# DUAL_M2_LEDS.net
KiCad netlist of a schematic drawn in EAGLE
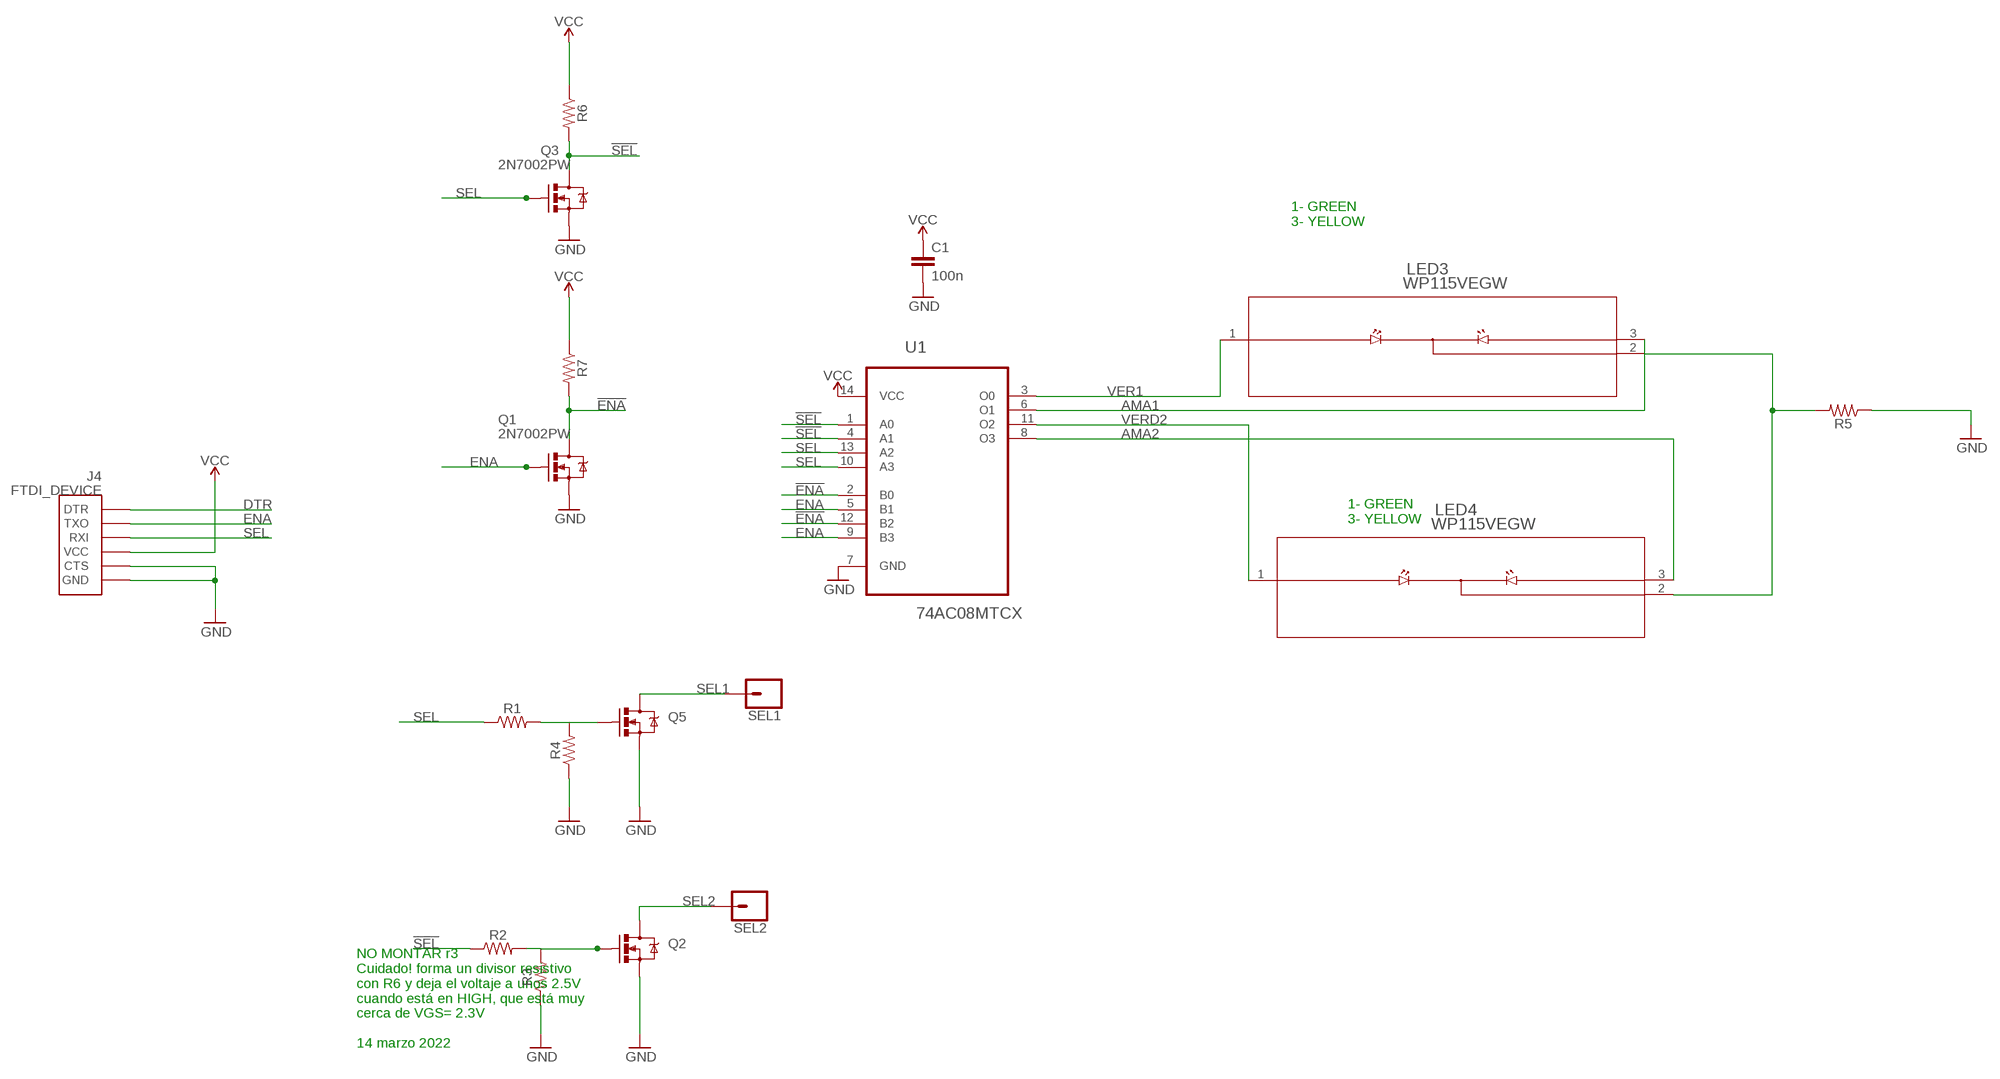
[diagram p0: schematic, sheet 1, part 1 of 2]
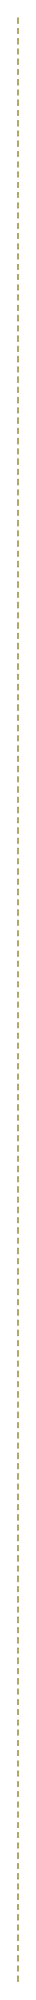
[diagram p1: schematic, sheet 1, part 2 of 2]

(export (version "E")
  (design (tool "Eeschema 10.0.6"))
  (components
    (comp (ref "C1")
      (value "100n")
      (footprint "eagle-import:0805")
      (libsource (lib "eagle-import") (part "CAPACITOR-N0805"))
    )
    (comp (ref "J4")
      (value "FTDI_DEVICE")
      (footprint "eagle-import:FTDI_DEVICE_SIDE")
      (libsource (lib "eagle-import") (part "FTDI_DEVICE"))
    )
    (comp (ref "LED3")
      (value "WP115VEGW")
      (footprint "eagle-import:WP115VEGW_KNB")
      (fields (field (name "COPYRIGHT") "Copyright (C) 2018 Accelerated Designs. All rights reserved"))
      (libsource (lib "eagle-import") (part "WP115VEGW"))
    )
    (comp (ref "LED4")
      (value "WP115VEGW")
      (footprint "eagle-import:WP115VEGW_KNB")
      (fields (field (name "COPYRIGHT") "Copyright (C) 2018 Accelerated Designs. All rights reserved"))
      (libsource (lib "eagle-import") (part "WP115VEGW"))
    )
    (comp (ref "Q1")
      (value "2N7002PW")
      (footprint "eagle-import:SOT323")
      (libsource (lib "eagle-import") (part "MOSFET-NCHANNEL2N7002PW"))
    )
    (comp (ref "Q2")
      (value "2N7002PW")
      (footprint "eagle-import:SOT323")
      (libsource (lib "eagle-import") (part "MOSFET-NCHANNEL2N7002PW"))
    )
    (comp (ref "Q3")
      (value "2N7002PW")
      (footprint "eagle-import:SOT323")
      (libsource (lib "eagle-import") (part "MOSFET-NCHANNEL2N7002PW"))
    )
    (comp (ref "Q5")
      (value "2N7002PW")
      (footprint "eagle-import:SOT323")
      (libsource (lib "eagle-import") (part "MOSFET-NCHANNEL2N7002PW"))
    )
    (comp (ref "R1")
      (value "RESISTOR0805")
      (footprint "eagle-import:0805")
      (libsource (lib "eagle-import") (part "RESISTOR0805"))
    )
    (comp (ref "R2")
      (value "RESISTOR0805")
      (footprint "eagle-import:0805")
      (libsource (lib "eagle-import") (part "RESISTOR0805"))
    )
    (comp (ref "R3")
      (value "RESISTOR0805")
      (footprint "eagle-import:0805")
      (libsource (lib "eagle-import") (part "RESISTOR0805"))
    )
    (comp (ref "R4")
      (value "RESISTOR0805")
      (footprint "eagle-import:0805")
      (libsource (lib "eagle-import") (part "RESISTOR0805"))
    )
    (comp (ref "R5")
      (value "RESISTOR0805")
      (footprint "eagle-import:0805")
      (libsource (lib "eagle-import") (part "RESISTOR0805"))
    )
    (comp (ref "R6")
      (value "RESISTOR0805")
      (footprint "eagle-import:0805")
      (libsource (lib "eagle-import") (part "RESISTOR0805"))
    )
    (comp (ref "R7")
      (value "RESISTOR0805")
      (footprint "eagle-import:0805")
      (libsource (lib "eagle-import") (part "RESISTOR0805"))
    )
    (comp (ref "SEL1")
      (value "CONN_01")
      (footprint "eagle-import:1X01")
      (libsource (lib "eagle-import") (part "CONN_01"))
    )
    (comp (ref "SEL2")
      (value "CONN_01")
      (footprint "eagle-import:1X01")
      (libsource (lib "eagle-import") (part "CONN_01"))
    )
    (comp (ref "U1")
      (value "74AC08MTCX")
      (footprint "eagle-import:SOP65P640X120-14N")
      (fields (field (name "MF") "ON"))
      (libsource (lib "eagle-import") (part "74AC08MTCX"))
    )
  )
  (nets
    (net (code "1") (name "/AMA1") (class "Default")
      (node (ref "LED3") (pin "3") (pinfunction "3_3") (pintype "passive"))
      (node (ref "U1") (pin "6") (pinfunction "O1_6") (pintype "output"))
    )
    (net (code "2") (name "/AMA2") (class "Default")
      (node (ref "LED4") (pin "3") (pinfunction "3_3") (pintype "passive"))
      (node (ref "U1") (pin "8") (pinfunction "O3_8") (pintype "output"))
    )
    (net (code "3") (name "/DTR") (class "Default")
      (node (ref "J4") (pin "P$1") (pinfunction "DTR_P$1") (pintype "bidirectional"))
    )
    (net (code "4") (name "/ENA") (class "Default")
      (node (ref "J4") (pin "P$2") (pinfunction "TXO_P$2") (pintype "bidirectional"))
      (node (ref "Q1") (pin "1") (pinfunction "G_1") (pintype "passive"))
      (node (ref "U1") (pin "5") (pinfunction "B1_5") (pintype "input"))
      (node (ref "U1") (pin "9") (pinfunction "B3_9") (pintype "input"))
    )
    (net (code "5") (name "/SEL") (class "Default")
      (node (ref "J4") (pin "P$3") (pinfunction "RXI_P$3") (pintype "bidirectional"))
      (node (ref "Q3") (pin "1") (pinfunction "G_1") (pintype "passive"))
      (node (ref "R1") (pin "1") (pinfunction "1_1") (pintype "passive"))
      (node (ref "U1") (pin "10") (pinfunction "A3_10") (pintype "input"))
      (node (ref "U1") (pin "13") (pinfunction "A2_13") (pintype "input"))
    )
    (net (code "6") (name "/SEL1") (class "Default")
      (node (ref "Q5") (pin "3") (pinfunction "D_3") (pintype "passive"))
      (node (ref "SEL1") (pin "1") (pinfunction "1_1") (pintype "passive"))
    )
    (net (code "7") (name "/SEL2") (class "Default")
      (node (ref "Q2") (pin "3") (pinfunction "D_3") (pintype "passive"))
      (node (ref "SEL2") (pin "1") (pinfunction "1_1") (pintype "passive"))
    )
    (net (code "8") (name "/VER1") (class "Default")
      (node (ref "LED3") (pin "1") (pinfunction "1_1") (pintype "passive"))
      (node (ref "U1") (pin "3") (pinfunction "O0_3") (pintype "output"))
    )
    (net (code "9") (name "/VERD2") (class "Default")
      (node (ref "LED4") (pin "1") (pinfunction "1_1") (pintype "passive"))
      (node (ref "U1") (pin "11") (pinfunction "O2_11") (pintype "output"))
    )
    (net (code "10") (name "/~{ENA}") (class "Default")
      (node (ref "Q1") (pin "3") (pinfunction "D_3") (pintype "passive"))
      (node (ref "R7") (pin "2") (pinfunction "2_2") (pintype "passive"))
      (node (ref "U1") (pin "12") (pinfunction "B2_12") (pintype "input"))
      (node (ref "U1") (pin "2") (pinfunction "B0_2") (pintype "input"))
    )
    (net (code "11") (name "/~{SEL}") (class "Default")
      (node (ref "Q3") (pin "3") (pinfunction "D_3") (pintype "passive"))
      (node (ref "R2") (pin "1") (pinfunction "1_1") (pintype "passive"))
      (node (ref "R6") (pin "2") (pinfunction "2_2") (pintype "passive"))
      (node (ref "U1") (pin "1") (pinfunction "A0_1") (pintype "input"))
      (node (ref "U1") (pin "4") (pinfunction "A1_4") (pintype "input"))
    )
    (net (code "12") (name "GND") (class "Default")
      (node (ref "C1") (pin "2") (pinfunction "2_2") (pintype "passive"))
      (node (ref "J4") (pin "P$5") (pinfunction "CTS_P$5") (pintype "bidirectional"))
      (node (ref "J4") (pin "P$6") (pinfunction "GND_P$6") (pintype "bidirectional"))
      (node (ref "Q1") (pin "2") (pinfunction "S_2") (pintype "passive"))
      (node (ref "Q2") (pin "2") (pinfunction "S_2") (pintype "passive"))
      (node (ref "Q3") (pin "2") (pinfunction "S_2") (pintype "passive"))
      (node (ref "Q5") (pin "2") (pinfunction "S_2") (pintype "passive"))
      (node (ref "R3") (pin "1") (pinfunction "1_1") (pintype "passive"))
      (node (ref "R4") (pin "1") (pinfunction "1_1") (pintype "passive"))
      (node (ref "R5") (pin "1") (pinfunction "1_1") (pintype "passive"))
      (node (ref "U1") (pin "7") (pinfunction "GND_7") (pintype "passive"))
    )
    (net (code "13") (name "Net-(LED3-Pad2)") (class "Default")
      (node (ref "LED3") (pin "2") (pinfunction "2_2") (pintype "passive"))
      (node (ref "LED4") (pin "2") (pinfunction "2_2") (pintype "passive"))
      (node (ref "R5") (pin "2") (pinfunction "2_2") (pintype "passive"))
    )
    (net (code "14") (name "Net-(Q2-G)") (class "Default")
      (node (ref "Q2") (pin "1") (pinfunction "G_1") (pintype "passive"))
      (node (ref "R2") (pin "2") (pinfunction "2_2") (pintype "passive"))
      (node (ref "R3") (pin "2") (pinfunction "2_2") (pintype "passive"))
    )
    (net (code "15") (name "Net-(Q5-G)") (class "Default")
      (node (ref "Q5") (pin "1") (pinfunction "G_1") (pintype "passive"))
      (node (ref "R1") (pin "2") (pinfunction "2_2") (pintype "passive"))
      (node (ref "R4") (pin "2") (pinfunction "2_2") (pintype "passive"))
    )
    (net (code "16") (name "VCC") (class "Default")
      (node (ref "C1") (pin "1") (pinfunction "1_1") (pintype "passive"))
      (node (ref "J4") (pin "P$4") (pinfunction "VCC_P$4") (pintype "bidirectional"))
      (node (ref "R6") (pin "1") (pinfunction "1_1") (pintype "passive"))
      (node (ref "R7") (pin "1") (pinfunction "1_1") (pintype "passive"))
      (node (ref "U1") (pin "14") (pinfunction "VCC_14") (pintype "power_in"))
    )
  )
)
